# 01_MAIN.net
KiCad netlist of a schematic drawn in Altium Designer
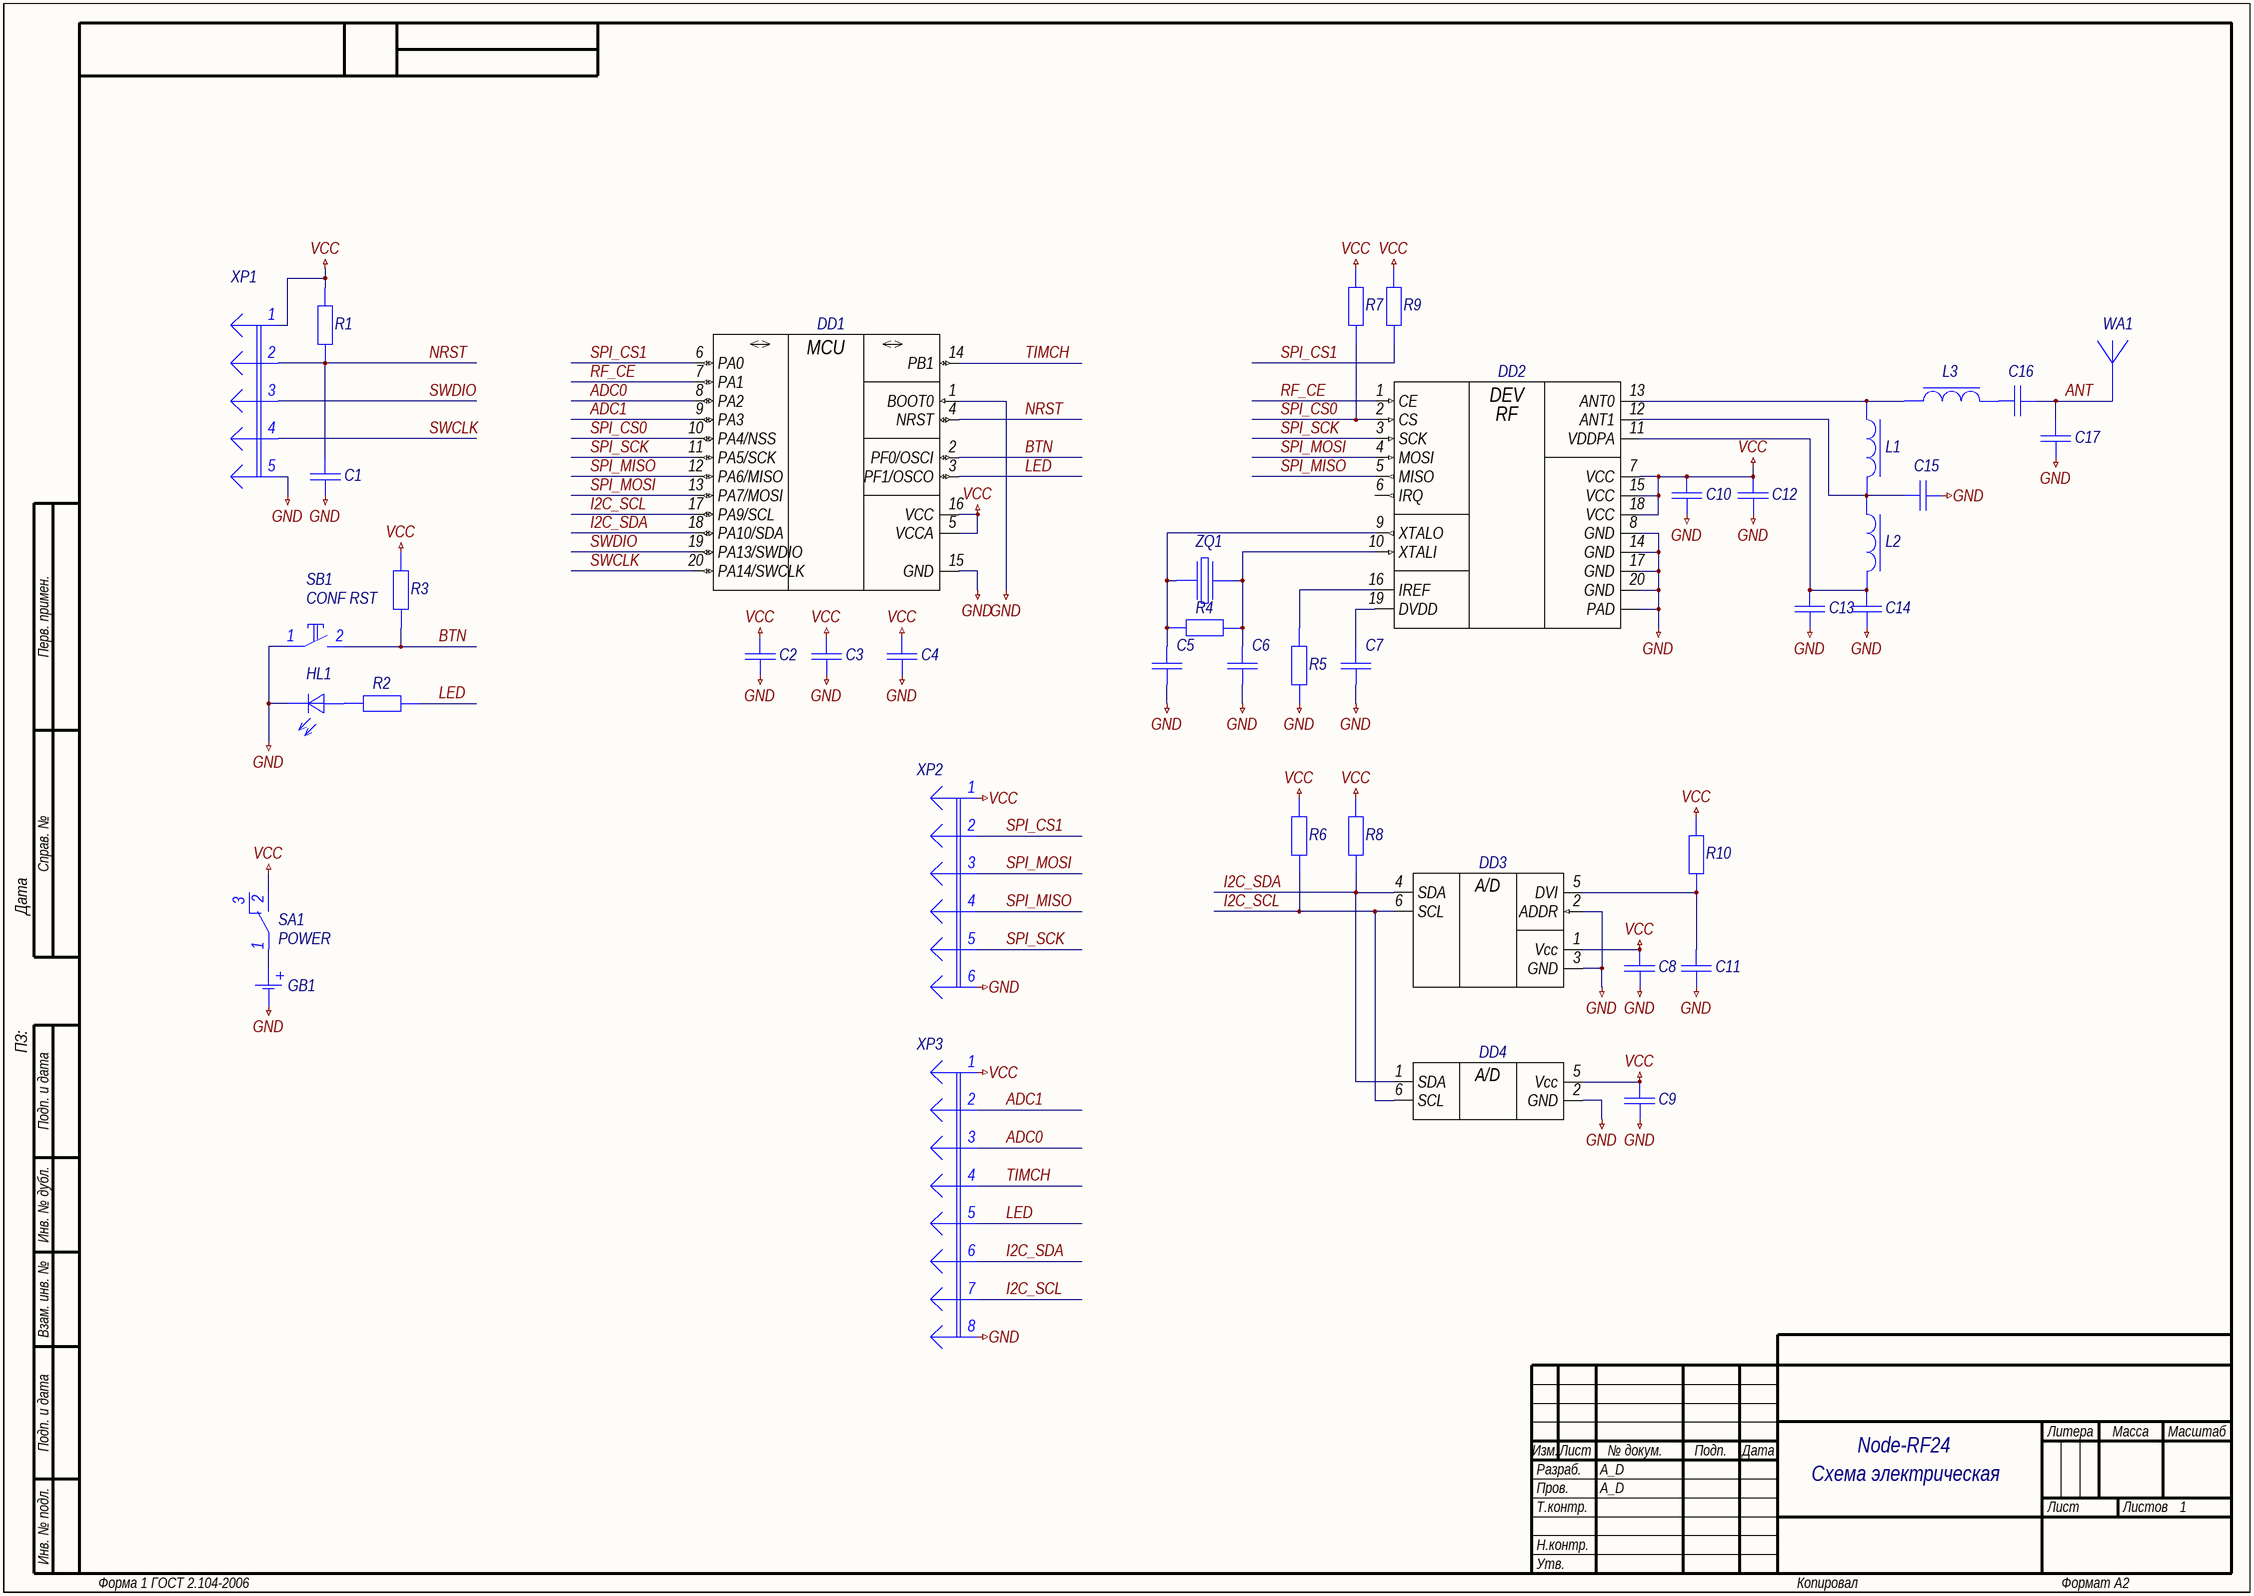
[diagram p0: 01_MAIN.SchDoc]

(export (version "E")
  (design (tool "Eeschema 10.0.6"))
  (components
    (comp (ref "C1")
      (value "Capacitor")
      (footprint "C0603_L")
      (fields
        (field (name "PART NUMBER") "GRM188R71C104KA01D")
        (field (name "VOLTAGE") "16V")
        (field (name "TOLERANCE") "±10%")
        (field (name "PUBLISHER") "Andrew Danich")
      )
      (libsource (lib "Lib_IMP_GOST") (part "Capacitor"))
    )
    (comp (ref "C2")
      (value "Capacitor")
      (footprint "C0805_L")
      (fields
        (field (name "PART NUMBER") "C0805C476M9PAC")
        (field (name "VOLTAGE") "6.3V")
        (field (name "TOLERANCE") "±20%")
        (field (name "PUBLISHER") "Andrew Danich")
      )
      (libsource (lib "Lib_IMP_GOST") (part "Capacitor"))
    )
    (comp (ref "C3")
      (value "Capacitor")
      (footprint "C0603_L")
      (fields
        (field (name "PART NUMBER") "GRM188R71C104KA01D")
        (field (name "VOLTAGE") "16V")
        (field (name "TOLERANCE") "±10%")
        (field (name "PUBLISHER") "Andrew Danich")
      )
      (libsource (lib "Lib_IMP_GOST") (part "Capacitor"))
    )
    (comp (ref "C4")
      (value "Capacitor")
      (footprint "C0603_L")
      (fields
        (field (name "PART NUMBER") "GRM188R71C104KA01D")
        (field (name "VOLTAGE") "16V")
        (field (name "TOLERANCE") "±10%")
        (field (name "PUBLISHER") "Andrew Danich")
      )
      (libsource (lib "Lib_IMP_GOST") (part "Capacitor"))
    )
    (comp (ref "C5")
      (value "Capacitor")
      (footprint "C0603_L")
      (fields
        (field (name "PART NUMBER") "GRM1885C1H120JA01D")
        (field (name "VOLTAGE") "50V")
        (field (name "TOLERANCE") "±5%")
        (field (name "PUBLISHER") "Andrew Danich")
      )
      (libsource (lib "Lib_IMP_GOST") (part "Capacitor"))
    )
    (comp (ref "C6")
      (value "Capacitor")
      (footprint "C0603_L")
      (fields
        (field (name "PART NUMBER") "GRM1885C1H120JA01D")
        (field (name "VOLTAGE") "50V")
        (field (name "TOLERANCE") "±5%")
        (field (name "PUBLISHER") "Andrew Danich")
      )
      (libsource (lib "Lib_IMP_GOST") (part "Capacitor"))
    )
    (comp (ref "C7")
      (value "Capacitor")
      (footprint "C0603_L")
      (fields
        (field (name "PART NUMBER") "GRM188R71E223KA01D")
        (field (name "VOLTAGE") "25V")
        (field (name "TOLERANCE") "±10%")
        (field (name "PUBLISHER") "Andrew Danich")
      )
      (libsource (lib "Lib_IMP_GOST") (part "Capacitor"))
    )
    (comp (ref "C8")
      (value "Capacitor")
      (footprint "C0603_L")
      (fields
        (field (name "PART NUMBER") "GRM188R71C104KA01D")
        (field (name "VOLTAGE") "16V")
        (field (name "TOLERANCE") "±10%")
        (field (name "PUBLISHER") "Andrew Danich")
      )
      (libsource (lib "Lib_IMP_GOST") (part "Capacitor"))
    )
    (comp (ref "C9")
      (value "Capacitor")
      (footprint "C0603_L")
      (fields
        (field (name "PART NUMBER") "GRM188R71C104KA01D")
        (field (name "VOLTAGE") "16V")
        (field (name "TOLERANCE") "±10%")
        (field (name "PUBLISHER") "Andrew Danich")
      )
      (libsource (lib "Lib_IMP_GOST") (part "Capacitor"))
    )
    (comp (ref "C10")
      (value "Capacitor")
      (footprint "C0603_L")
      (fields
        (field (name "PART NUMBER") "C0603C103J5RAC")
        (field (name "VOLTAGE") "50V")
        (field (name "TOLERANCE") "±5%")
        (field (name "PUBLISHER") "Andrew Danich")
      )
      (libsource (lib "Lib_IMP_GOST") (part "Capacitor"))
    )
    (comp (ref "C11")
      (value "Capacitor")
      (footprint "C0603_L")
      (fields
        (field (name "PART NUMBER") "GRM188R71C104KA01D")
        (field (name "VOLTAGE") "16V")
        (field (name "TOLERANCE") "±10%")
        (field (name "PUBLISHER") "Andrew Danich")
      )
      (libsource (lib "Lib_IMP_GOST") (part "Capacitor"))
    )
    (comp (ref "C12")
      (value "Capacitor")
      (footprint "C0603_L")
      (fields
        (field (name "PART NUMBER") "C0603C102J5GAC")
        (field (name "VOLTAGE") "50V")
        (field (name "TOLERANCE") "±5%")
        (field (name "PUBLISHER") "Andrew Danich")
      )
      (libsource (lib "Lib_IMP_GOST") (part "Capacitor"))
    )
    (comp (ref "C13")
      (value "Capacitor")
      (footprint "C0603_L")
      (fields
        (field (name "PART NUMBER") "C0603C222J5GAC")
        (field (name "VOLTAGE") "50V")
        (field (name "TOLERANCE") "±5%")
        (field (name "PUBLISHER") "Andrew Danich")
      )
      (libsource (lib "Lib_IMP_GOST") (part "Capacitor"))
    )
    (comp (ref "C14")
      (value "Capacitor")
      (footprint "C0603_L")
      (fields
        (field (name "PART NUMBER") "C0603C479K5GAC")
        (field (name "VOLTAGE") "50V")
        (field (name "TOLERANCE") "±10%")
        (field (name "PUBLISHER") "Andrew Danich")
      )
      (libsource (lib "Lib_IMP_GOST") (part "Capacitor"))
    )
    (comp (ref "C15")
      (value "Capacitor")
      (footprint "C0603_L")
      (fields
        (field (name "PART NUMBER") "C0603C229C5GAC")
        (field (name "VOLTAGE") "50V")
        (field (name "MANUFACTURER") "Kemet")
        (field (name "PUBLISHER") "Andrew Danich")
      )
      (libsource (lib "Lib_IMP_GOST") (part "Capacitor"))
    )
    (comp (ref "C16")
      (value "Capacitor")
      (footprint "C0603_L")
      (fields
        (field (name "PART NUMBER") "C0603C229C5GAC")
        (field (name "VOLTAGE") "50V")
        (field (name "MANUFACTURER") "Kemet")
        (field (name "PUBLISHER") "Andrew Danich")
      )
      (libsource (lib "Lib_IMP_GOST") (part "Capacitor"))
    )
    (comp (ref "C17")
      (value "Capacitor")
      (footprint "C0603_L")
      (fields
        (field (name "PART NUMBER") "C0603C229C5GAC")
        (field (name "VOLTAGE") "50V")
        (field (name "MANUFACTURER") "Kemet")
        (field (name "PUBLISHER") "Andrew Danich")
      )
      (libsource (lib "Lib_IMP_GOST") (part "Capacitor"))
    )
    (comp (ref "DD1")
      (value "STM32F030Fx_20p")
      (footprint "TSSOP-20W")
      (fields
        (field (name "PART NUMBER") "STM32F030F4P6")
        (field (name "MANUFACTURER") "STMicroelectronics")
        (field (name "PUBLISHER") "Andrew Danich")
      )
      (libsource (lib "Lib_IMP_GOST") (part "STM32F030Fx_20p"))
    )
    (comp (ref "DD2")
      (value "nRF24L01")
      (footprint "QFN-20-NRF24L01")
      (description "Single Chip 2.4GHz Transceiver")
      (fields (field (name "PART NUMBER") "nRF24L01+") (field (name "PUBLISHER") "Andrew Danich"))
      (libsource (lib "Lib_IMP_GOST") (part "nRF24L01"))
    )
    (comp (ref "DD3")
      (value "BH1750")
      (footprint "WSOF-6I")
      (fields
        (field (name "PART NUMBER") "BH1750FVI")
        (field (name "MANUFACTURER") "ROHM")
        (field (name "PUBLISHER") "Andrew Danich")
      )
      (libsource (lib "Lib_IMP_GOST") (part "BH1750"))
    )
    (comp (ref "DD4")
      (value "Si7021")
      (footprint "DFN-6-PC")
      (fields
        (field (name "PART NUMBER") "Si7021-A20-GM1")
        (field (name "MANUFACTURER") "Silicon Labs")
        (field (name "PUBLISHER") "Andrew Danich")
      )
      (libsource (lib "Lib_IMP_GOST") (part "Si7021"))
    )
    (comp (ref "GB1")
      (value "Text")
      (footprint "BS-2450")
      (fields
        (field (name "PART NUMBER") "BS-2450")
        (field (name "MANUFACTURER") "Memory Protection Devices")
        (field (name "PUBLISHER") "Andrew Danich")
      )
      (libsource (lib "Lib_IMP_GOST") (part "BH-01x"))
    )
    (comp (ref "HL1")
      (value "Text")
      (footprint "LD0603_L")
      (fields (field (name "PART NUMBER") "BL-LS0603GC") (field (name "PUBLISHER") "Andrew Danich"))
      (libsource (lib "Lib_IMP_GOST") (part "Led-1"))
    )
    (comp (ref "L1")
      (value "Coil")
      (footprint "L0603_L")
      (fields
        (field (name "PART NUMBER") "LQG18HN8N2J00")
        (field (name "TOLERANCE") "±5%")
        (field (name "MANUFACTURER") "Murata")
        (field (name "PUBLISHER") "Andrew Danich")
      )
      (libsource (lib "Lib_IMP_GOST") (part "Coil"))
    )
    (comp (ref "L2")
      (value "Coil")
      (footprint "L0603_L")
      (fields
        (field (name "PART NUMBER") "LQG18HN2N7S00")
        (field (name "TOLERANCE") "±0.3nH")
        (field (name "MANUFACTURER") "Murata")
        (field (name "PUBLISHER") "Andrew Danich")
      )
      (libsource (lib "Lib_IMP_GOST") (part "Coil"))
    )
    (comp (ref "L3")
      (value "Coil")
      (footprint "L0603_L")
      (fields
        (field (name "PART NUMBER") "LQG18HN3N9S00")
        (field (name "TOLERANCE") "±0.3nH")
        (field (name "MANUFACTURER") "Murata")
        (field (name "PUBLISHER") "Andrew Danich")
      )
      (libsource (lib "Lib_IMP_GOST") (part "Coil"))
    )
    (comp (ref "R1")
      (value "Resistor")
      (footprint "R0603_L")
      (fields
        (field (name "PART NUMBER") "RC0603JR-0710KL")
        (field (name "TOLERANCE") "±5%")
        (field (name "MANUFACTURER") "Yageo")
        (field (name "PUBLISHER") "Andrew Danich")
      )
      (libsource (lib "Lib_IMP_GOST") (part "Resistor"))
    )
    (comp (ref "R2")
      (value "Resistor")
      (footprint "R0603_L")
      (fields
        (field (name "PART NUMBER") "RC0603JR-071KL")
        (field (name "TOLERANCE") "±5%")
        (field (name "MANUFACTURER") "Yageo")
        (field (name "PUBLISHER") "Andrew Danich")
      )
      (libsource (lib "Lib_IMP_GOST") (part "Resistor"))
    )
    (comp (ref "R3")
      (value "Resistor")
      (footprint "R0603_L")
      (fields
        (field (name "PART NUMBER") "RC0603JR-0710KL")
        (field (name "TOLERANCE") "±5%")
        (field (name "MANUFACTURER") "Yageo")
        (field (name "PUBLISHER") "Andrew Danich")
      )
      (libsource (lib "Lib_IMP_GOST") (part "Resistor"))
    )
    (comp (ref "R4")
      (value "Resistor")
      (footprint "R0603_L")
      (fields
        (field (name "PART NUMBER") "RC0603JR-071ML")
        (field (name "TOLERANCE") "±5%")
        (field (name "MANUFACTURER") "Yageo")
        (field (name "PUBLISHER") "Andrew Danich")
      )
      (libsource (lib "Lib_IMP_GOST") (part "Resistor"))
    )
    (comp (ref "R5")
      (value "Resistor")
      (footprint "R0603_L")
      (fields
        (field (name "PART NUMBER") "RC0603JR-0722KL")
        (field (name "TOLERANCE") "±5%")
        (field (name "MANUFACTURER") "Yageo")
        (field (name "PUBLISHER") "Andrew Danich")
      )
      (libsource (lib "Lib_IMP_GOST") (part "Resistor"))
    )
    (comp (ref "R6")
      (value "Resistor")
      (footprint "R0603_L")
      (fields
        (field (name "PART NUMBER") "RC0603JR-0710KL")
        (field (name "TOLERANCE") "±5%")
        (field (name "MANUFACTURER") "Yageo")
        (field (name "PUBLISHER") "Andrew Danich")
      )
      (libsource (lib "Lib_IMP_GOST") (part "Resistor"))
    )
    (comp (ref "R7")
      (value "Resistor")
      (footprint "R0603_L")
      (fields
        (field (name "PART NUMBER") "RC0603JR-0710KL")
        (field (name "TOLERANCE") "±5%")
        (field (name "MANUFACTURER") "Yageo")
        (field (name "PUBLISHER") "Andrew Danich")
      )
      (libsource (lib "Lib_IMP_GOST") (part "Resistor"))
    )
    (comp (ref "R8")
      (value "Resistor")
      (footprint "R0603_L")
      (fields
        (field (name "PART NUMBER") "RC0603JR-0710KL")
        (field (name "TOLERANCE") "±5%")
        (field (name "MANUFACTURER") "Yageo")
        (field (name "PUBLISHER") "Andrew Danich")
      )
      (libsource (lib "Lib_IMP_GOST") (part "Resistor"))
    )
    (comp (ref "R9")
      (value "Resistor")
      (footprint "R0603_L")
      (fields
        (field (name "PART NUMBER") "RC0603JR-0710KL")
        (field (name "TOLERANCE") "±5%")
        (field (name "MANUFACTURER") "Yageo")
        (field (name "PUBLISHER") "Andrew Danich")
      )
      (libsource (lib "Lib_IMP_GOST") (part "Resistor"))
    )
    (comp (ref "R10")
      (value "Resistor")
      (footprint "R0603_L")
      (fields
        (field (name "PART NUMBER") "RC0603JR-071KL")
        (field (name "TOLERANCE") "±5%")
        (field (name "MANUFACTURER") "Yageo")
        (field (name "PUBLISHER") "Andrew Danich")
      )
      (libsource (lib "Lib_IMP_GOST") (part "Resistor"))
    )
    (comp (ref "SA1")
      (value "POWER")
      (footprint "SS-12F21")
      (fields (field (name "PART NUMBER") "SS-12F21") (field (name "PUBLISHER") "Andrew Danich"))
      (libsource (lib "Lib_IMP_GOST") (part "SW-01x-02p"))
    )
    (comp (ref "SB1")
      (value "CONF RST")
      (footprint "DTSM-32")
      (fields (field (name "PART NUMBER") "DTSM-32") (field (name "PUBLISHER") "Andrew Danich"))
      (libsource (lib "Lib_IMP_GOST") (part "BT-01x-01p"))
    )
    (comp (ref "WA1")
      (value "Antenna_US_1p")
      (footprint "AN9520")
      (fields
        (field (name "PART NUMBER") "AN9520")
        (field (name "MANUFACTURER") "RainSun")
        (field (name "PUBLISHER") "A_D")
      )
      (libsource (lib "Lib_IMP_GOST") (part "Antenna_US_1p"))
    )
    (comp (ref "XP1")
      (value "SWD")
      (footprint "PLS-5")
      (fields (field (name "PART NUMBER") "PLS-5") (field (name "PUBLISHER") "Andrew Danich"))
      (libsource (lib "Lib_IMP_GOST") (part "Con-5-M"))
    )
    (comp (ref "XP2")
      (value "SPI")
      (footprint "PLS-6")
      (fields (field (name "PART NUMBER") "PLS-6") (field (name "PUBLISHER") "Andrew Danich"))
      (libsource (lib "Lib_IMP_GOST") (part "Con-6-M"))
    )
    (comp (ref "XP3")
      (value "IO")
      (footprint "PLS-8")
      (fields (field (name "PART NUMBER") "PLS-8") (field (name "PUBLISHER") "Andrew Danich"))
      (libsource (lib "Lib_IMP_GOST") (part "Con-8-M"))
    )
    (comp (ref "ZQ1")
      (value "Crystal")
      (footprint "SX-3225")
      (fields (field (name "PART NUMBER") "SX-3225 16.000MHz") (field (name "PUBLISHER") "Andrew Danich"))
      (libsource (lib "Lib_IMP_GOST") (part "Crystal"))
    )
  )
  (nets
    (net (code "1") (name "/ADC0") (class "Default")
      (node (ref "DD1") (pin "8") (pinfunction "PA2_8") (pintype "bidirectional"))
      (node (ref "XP3") (pin "3") (pintype "passive"))
    )
    (net (code "2") (name "/ADC1") (class "Default")
      (node (ref "DD1") (pin "9") (pinfunction "PA3_9") (pintype "bidirectional"))
      (node (ref "XP3") (pin "2") (pintype "passive"))
    )
    (net (code "3") (name "/ANT") (class "Default")
      (node (ref "C16") (pin "1") (pinfunction "1_1") (pintype "passive"))
      (node (ref "C17") (pin "1") (pinfunction "1_1") (pintype "passive"))
      (node (ref "WA1") (pin "1") (pinfunction "1_1") (pintype "passive"))
    )
    (net (code "4") (name "/BTN") (class "Default")
      (node (ref "DD1") (pin "2") (pinfunction "PF0/OSCI_2") (pintype "bidirectional"))
      (node (ref "R3") (pin "1") (pinfunction "1_1") (pintype "passive"))
      (node (ref "SB1") (pin "2") (pintype "passive"))
    )
    (net (code "5") (name "/I2C_SCL") (class "Default")
      (node (ref "DD1") (pin "17") (pinfunction "PA9/SCL_17") (pintype "bidirectional"))
      (node (ref "DD3") (pin "6") (pinfunction "SCL_6") (pintype "open_collector"))
      (node (ref "DD4") (pin "6") (pinfunction "SCL_6") (pintype "open_collector"))
      (node (ref "R6") (pin "1") (pinfunction "1_1") (pintype "passive"))
      (node (ref "XP3") (pin "7") (pintype "passive"))
    )
    (net (code "6") (name "/I2C_SDA") (class "Default")
      (node (ref "DD1") (pin "18") (pinfunction "PA10/SDA_18") (pintype "bidirectional"))
      (node (ref "DD3") (pin "4") (pinfunction "SDA_4") (pintype "open_collector"))
      (node (ref "DD4") (pin "1") (pinfunction "SDA_1") (pintype "open_collector"))
      (node (ref "R8") (pin "1") (pinfunction "1_1") (pintype "passive"))
      (node (ref "XP3") (pin "6") (pintype "passive"))
    )
    (net (code "7") (name "/LED") (class "Default")
      (node (ref "DD1") (pin "3") (pinfunction "PF1/OSCO_3") (pintype "bidirectional"))
      (node (ref "R2") (pin "2") (pinfunction "2_2") (pintype "passive"))
      (node (ref "XP3") (pin "5") (pintype "passive"))
    )
    (net (code "8") (name "/NRST") (class "Default")
      (node (ref "C1") (pin "2") (pinfunction "2_2") (pintype "passive"))
      (node (ref "DD1") (pin "4") (pinfunction "NRST_4") (pintype "bidirectional"))
      (node (ref "R1") (pin "1") (pinfunction "1_1") (pintype "passive"))
      (node (ref "XP1") (pin "2") (pintype "passive"))
    )
    (net (code "9") (name "/RF_CE") (class "Default")
      (node (ref "DD1") (pin "7") (pinfunction "PA1_7") (pintype "bidirectional"))
      (node (ref "DD2") (pin "1") (pinfunction "CE_1") (pintype "input"))
    )
    (net (code "10") (name "/SPI_CS0") (class "Default")
      (node (ref "DD1") (pin "10") (pinfunction "PA4/NSS_10") (pintype "bidirectional"))
      (node (ref "DD2") (pin "2") (pinfunction "CS_2") (pintype "input"))
      (node (ref "R7") (pin "1") (pinfunction "1_1") (pintype "passive"))
    )
    (net (code "11") (name "/SPI_CS1") (class "Default")
      (node (ref "DD1") (pin "6") (pinfunction "PA0_6") (pintype "bidirectional"))
      (node (ref "R9") (pin "1") (pinfunction "1_1") (pintype "passive"))
      (node (ref "XP2") (pin "2") (pintype "passive"))
    )
    (net (code "12") (name "/SPI_MISO") (class "Default")
      (node (ref "DD1") (pin "12") (pinfunction "PA6/MISO_12") (pintype "bidirectional"))
      (node (ref "DD2") (pin "5") (pinfunction "MISO_5") (pintype "output"))
      (node (ref "XP2") (pin "4") (pintype "passive"))
    )
    (net (code "13") (name "/SPI_MOSI") (class "Default")
      (node (ref "DD1") (pin "13") (pinfunction "PA7/MOSI_13") (pintype "bidirectional"))
      (node (ref "DD2") (pin "4") (pinfunction "MOSI_4") (pintype "input"))
      (node (ref "XP2") (pin "3") (pintype "passive"))
    )
    (net (code "14") (name "/SPI_SCK") (class "Default")
      (node (ref "DD1") (pin "11") (pinfunction "PA5/SCK_11") (pintype "bidirectional"))
      (node (ref "DD2") (pin "3") (pinfunction "SCK_3") (pintype "input"))
      (node (ref "XP2") (pin "5") (pintype "passive"))
    )
    (net (code "15") (name "/SWCLK") (class "Default")
      (node (ref "DD1") (pin "20") (pinfunction "PA14/SWCLK_20") (pintype "bidirectional"))
      (node (ref "XP1") (pin "4") (pintype "passive"))
    )
    (net (code "16") (name "/SWDIO") (class "Default")
      (node (ref "DD1") (pin "19") (pinfunction "PA13/SWDIO_19") (pintype "bidirectional"))
      (node (ref "XP1") (pin "3") (pintype "passive"))
    )
    (net (code "17") (name "/TIMCH") (class "Default")
      (node (ref "DD1") (pin "14") (pinfunction "PB1_14") (pintype "bidirectional"))
      (node (ref "XP3") (pin "4") (pintype "passive"))
    )
    (net (code "18") (name "GND") (class "Default")
      (node (ref "C1") (pin "1") (pinfunction "1_1") (pintype "passive"))
      (node (ref "C10") (pin "1") (pinfunction "1_1") (pintype "passive"))
      (node (ref "C11") (pin "1") (pinfunction "1_1") (pintype "passive"))
      (node (ref "C12") (pin "1") (pinfunction "1_1") (pintype "passive"))
      (node (ref "C13") (pin "1") (pinfunction "1_1") (pintype "passive"))
      (node (ref "C14") (pin "1") (pinfunction "1_1") (pintype "passive"))
      (node (ref "C15") (pin "1") (pinfunction "1_1") (pintype "passive"))
      (node (ref "C17") (pin "2") (pinfunction "2_2") (pintype "passive"))
      (node (ref "C2") (pin "1") (pinfunction "1_1") (pintype "passive"))
      (node (ref "C3") (pin "1") (pinfunction "1_1") (pintype "passive"))
      (node (ref "C4") (pin "1") (pinfunction "1_1") (pintype "passive"))
      (node (ref "C5") (pin "1") (pinfunction "1_1") (pintype "passive"))
      (node (ref "C6") (pin "1") (pinfunction "1_1") (pintype "passive"))
      (node (ref "C7") (pin "1") (pinfunction "1_1") (pintype "passive"))
      (node (ref "C8") (pin "1") (pinfunction "1_1") (pintype "passive"))
      (node (ref "C9") (pin "1") (pinfunction "1_1") (pintype "passive"))
      (node (ref "DD1") (pin "1") (pinfunction "BOOT0_1") (pintype "input"))
      (node (ref "DD1") (pin "15") (pinfunction "GND_15") (pintype "power_in"))
      (node (ref "DD2") (pin "14") (pinfunction "GND_14") (pintype "power_in"))
      (node (ref "DD2") (pin "17") (pinfunction "GND_17") (pintype "power_in"))
      (node (ref "DD2") (pin "20") (pinfunction "GND_20") (pintype "power_in"))
      (node (ref "DD2") (pin "21") (pinfunction "PAD_21") (pintype "power_in"))
      (node (ref "DD2") (pin "8") (pinfunction "GND_8") (pintype "power_in"))
      (node (ref "DD3") (pin "2") (pinfunction "ADDR_2") (pintype "input"))
      (node (ref "DD3") (pin "3") (pinfunction "GND_3") (pintype "power_in"))
      (node (ref "DD4") (pin "2") (pinfunction "GND_2") (pintype "power_in"))
      (node (ref "GB1") (pin "2") (pinfunction "-_2") (pintype "passive"))
      (node (ref "HL1") (pin "2") (pinfunction "К_2") (pintype "passive"))
      (node (ref "R5") (pin "1") (pinfunction "1_1") (pintype "passive"))
      (node (ref "SB1") (pin "1") (pintype "passive"))
      (node (ref "XP1") (pin "5") (pintype "passive"))
      (node (ref "XP2") (pin "6") (pintype "passive"))
      (node (ref "XP3") (pin "8") (pintype "passive"))
    )
    (net (code "19") (name "Net-(C16-Pad2)") (class "Default")
      (node (ref "C16") (pin "2") (pinfunction "2_2") (pintype "passive"))
      (node (ref "L3") (pin "2") (pinfunction "2_2") (pintype "passive"))
    )
    (net (code "20") (name "Net-(DD2-ANT0)") (class "Default")
      (node (ref "DD2") (pin "13") (pinfunction "ANT0_13") (pintype "passive"))
      (node (ref "L1") (pin "1") (pinfunction "1_1") (pintype "passive"))
      (node (ref "L3") (pin "1") (pinfunction "1_1") (pintype "passive"))
    )
    (net (code "21") (name "Net-(DD2-ANT1)") (class "Default")
      (node (ref "C15") (pin "2") (pinfunction "2_2") (pintype "passive"))
      (node (ref "DD2") (pin "12") (pinfunction "ANT1_12") (pintype "passive"))
      (node (ref "L1") (pin "2") (pinfunction "2_2") (pintype "passive"))
      (node (ref "L2") (pin "1") (pinfunction "1_1") (pintype "passive"))
    )
    (net (code "22") (name "Net-(DD2-DVDD)") (class "Default")
      (node (ref "C7") (pin "2") (pinfunction "2_2") (pintype "passive"))
      (node (ref "DD2") (pin "19") (pinfunction "DVDD_19") (pintype "power_in"))
    )
    (net (code "23") (name "Net-(DD2-IREF)") (class "Default")
      (node (ref "DD2") (pin "16") (pinfunction "IREF_16") (pintype "passive"))
      (node (ref "R5") (pin "2") (pinfunction "2_2") (pintype "passive"))
    )
    (net (code "24") (name "Net-(DD2-VDDPA)") (class "Default")
      (node (ref "C13") (pin "2") (pinfunction "2_2") (pintype "passive"))
      (node (ref "C14") (pin "2") (pinfunction "2_2") (pintype "passive"))
      (node (ref "DD2") (pin "11") (pinfunction "VDDPA_11") (pintype "power_in"))
      (node (ref "L2") (pin "2") (pinfunction "2_2") (pintype "passive"))
    )
    (net (code "25") (name "Net-(DD2-XTALI)") (class "Default")
      (node (ref "C6") (pin "2") (pinfunction "2_2") (pintype "passive"))
      (node (ref "DD2") (pin "10") (pinfunction "XTALI_10") (pintype "input"))
      (node (ref "R4") (pin "2") (pinfunction "2_2") (pintype "passive"))
      (node (ref "ZQ1") (pin "3") (pinfunction "3_3") (pintype "passive"))
    )
    (net (code "26") (name "Net-(DD2-XTALO)") (class "Default")
      (node (ref "C5") (pin "2") (pinfunction "2_2") (pintype "passive"))
      (node (ref "DD2") (pin "9") (pinfunction "XTALO_9") (pintype "output"))
      (node (ref "R4") (pin "1") (pinfunction "1_1") (pintype "passive"))
      (node (ref "ZQ1") (pin "1") (pinfunction "1_1") (pintype "passive"))
    )
    (net (code "27") (name "Net-(DD3-DVI)") (class "Default")
      (node (ref "C11") (pin "2") (pinfunction "2_2") (pintype "passive"))
      (node (ref "DD3") (pin "5") (pinfunction "DVI_5") (pintype "power_in"))
      (node (ref "R10") (pin "1") (pinfunction "1_1") (pintype "passive"))
    )
    (net (code "28") (name "Net-(GB1-+)") (class "Default")
      (node (ref "GB1") (pin "1") (pinfunction "+_1") (pintype "passive"))
      (node (ref "SA1") (pin "1") (pinfunction "A1_1") (pintype "passive"))
    )
    (net (code "29") (name "Net-(HL1-А)") (class "Default")
      (node (ref "HL1") (pin "1") (pinfunction "А_1") (pintype "passive"))
      (node (ref "R2") (pin "1") (pinfunction "1_1") (pintype "passive"))
    )
    (net (code "30") (name "VCC") (class "Default")
      (node (ref "C10") (pin "2") (pinfunction "2_2") (pintype "passive"))
      (node (ref "C12") (pin "2") (pinfunction "2_2") (pintype "passive"))
      (node (ref "C2") (pin "2") (pinfunction "2_2") (pintype "passive"))
      (node (ref "C3") (pin "2") (pinfunction "2_2") (pintype "passive"))
      (node (ref "C4") (pin "2") (pinfunction "2_2") (pintype "passive"))
      (node (ref "C8") (pin "2") (pinfunction "2_2") (pintype "passive"))
      (node (ref "C9") (pin "2") (pinfunction "2_2") (pintype "passive"))
      (node (ref "DD1") (pin "16") (pinfunction "VCC_16") (pintype "power_in"))
      (node (ref "DD1") (pin "5") (pinfunction "VCCA_5") (pintype "power_in"))
      (node (ref "DD2") (pin "15") (pinfunction "VCC_15") (pintype "power_in"))
      (node (ref "DD2") (pin "18") (pinfunction "VCC_18") (pintype "power_in"))
      (node (ref "DD2") (pin "7") (pinfunction "VCC_7") (pintype "power_in"))
      (node (ref "DD3") (pin "1") (pinfunction "Vcc_1") (pintype "power_in"))
      (node (ref "DD4") (pin "5") (pinfunction "Vcc_5") (pintype "power_in"))
      (node (ref "R1") (pin "2") (pinfunction "2_2") (pintype "passive"))
      (node (ref "R10") (pin "2") (pinfunction "2_2") (pintype "passive"))
      (node (ref "R3") (pin "2") (pinfunction "2_2") (pintype "passive"))
      (node (ref "R6") (pin "2") (pinfunction "2_2") (pintype "passive"))
      (node (ref "R7") (pin "2") (pinfunction "2_2") (pintype "passive"))
      (node (ref "R8") (pin "2") (pinfunction "2_2") (pintype "passive"))
      (node (ref "R9") (pin "2") (pinfunction "2_2") (pintype "passive"))
      (node (ref "SA1") (pin "2") (pinfunction "B1_2") (pintype "passive"))
      (node (ref "XP1") (pin "1") (pintype "passive"))
      (node (ref "XP2") (pin "1") (pintype "passive"))
      (node (ref "XP3") (pin "1") (pintype "passive"))
    )
    (net (code "31") (name "unconnected-(DD2-IRQ-Pad6)") (class "Default")
      (node (ref "DD2") (pin "6") (pinfunction "IRQ_6") (pintype "output"))
    )
    (net (code "32") (name "unconnected-(SA1-C1-Pad3)") (class "Default")
      (node (ref "SA1") (pin "3") (pinfunction "C1_3") (pintype "passive"))
    )
  )
)
